# plate.net
KiCad netlist of a schematic drawn in Altium Designer
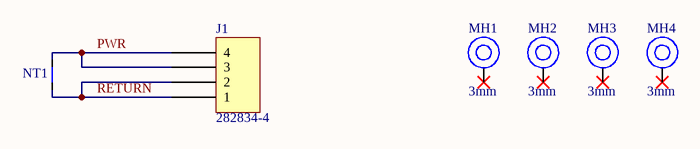
[diagram p0: plate.SchDoc]

(export (version "E")
  (design (tool "Eeschema 10.0.6"))
  (components
    (comp (ref "J1")
      (value "282834-4")
      (footprint "TE 282834-4")
      (description "TERM BLK 4P SIDE ENT 2.54MM PCB")
      (fields (field (name "MANUFACTURER") "TE Connectivity AMP Connectors") (field (name "VOLTAGE") "150V"))
      (libsource (lib "Celestial Altium Library - altium_library") (part "4 Pin"))
    )
    (comp (ref "MH1")
      (value "3mm")
      (footprint "Mount-Hole_3mm")
      (description "Mounting Hole 3mm plated")
      (libsource (lib "Schlib1") (part "Mount_Hole_3mm"))
    )
    (comp (ref "MH2")
      (value "3mm")
      (footprint "Mount-Hole_3mm")
      (description "Mounting Hole 3mm plated")
      (libsource (lib "Schlib1") (part "Mount_Hole_3mm"))
    )
    (comp (ref "MH3")
      (value "3mm")
      (footprint "Mount-Hole_3mm")
      (description "Mounting Hole 3mm plated")
      (libsource (lib "Schlib1") (part "Mount_Hole_3mm"))
    )
    (comp (ref "MH4")
      (value "3mm")
      (footprint "Mount-Hole_3mm")
      (description "Mounting Hole 3mm plated")
      (libsource (lib "Schlib1") (part "Mount_Hole_3mm"))
    )
    (comp (ref "NT1")
      (value "Net Tie")
      (footprint "NetTie_50mil")
      (description "Net Tie with 50mil trace")
      (libsource (lib "Schlib1") (part "NetTie_50mil"))
    )
  )
  (nets
    (net (code "1") (name "/PWR") (class "Default")
      (node (ref "J1") (pin "3") (pinfunction "3_3") (pintype "passive"))
      (node (ref "J1") (pin "4") (pinfunction "4_4") (pintype "passive"))
      (node (ref "NT1") (pin "2") (pinfunction "2_2") (pintype "passive"))
    )
    (net (code "2") (name "/RETURN") (class "Default")
      (node (ref "J1") (pin "1") (pinfunction "1_1") (pintype "passive"))
      (node (ref "J1") (pin "2") (pinfunction "2_2") (pintype "passive"))
      (node (ref "NT1") (pin "1") (pinfunction "1_1") (pintype "passive"))
    )
    (net (code "3") (name "unconnected-(MH1-Pad1)") (class "Default")
      (node (ref "MH1") (pin "1") (pinfunction "1_1") (pintype "passive+no_connect"))
    )
    (net (code "4") (name "unconnected-(MH2-Pad1)") (class "Default")
      (node (ref "MH2") (pin "1") (pinfunction "1_1") (pintype "passive+no_connect"))
    )
    (net (code "5") (name "unconnected-(MH3-Pad1)") (class "Default")
      (node (ref "MH3") (pin "1") (pinfunction "1_1") (pintype "passive+no_connect"))
    )
    (net (code "6") (name "unconnected-(MH4-Pad1)") (class "Default")
      (node (ref "MH4") (pin "1") (pinfunction "1_1") (pintype "passive+no_connect"))
    )
  )
)
